# micro_RevB-328.net
KiCad netlist of a schematic drawn in EAGLE
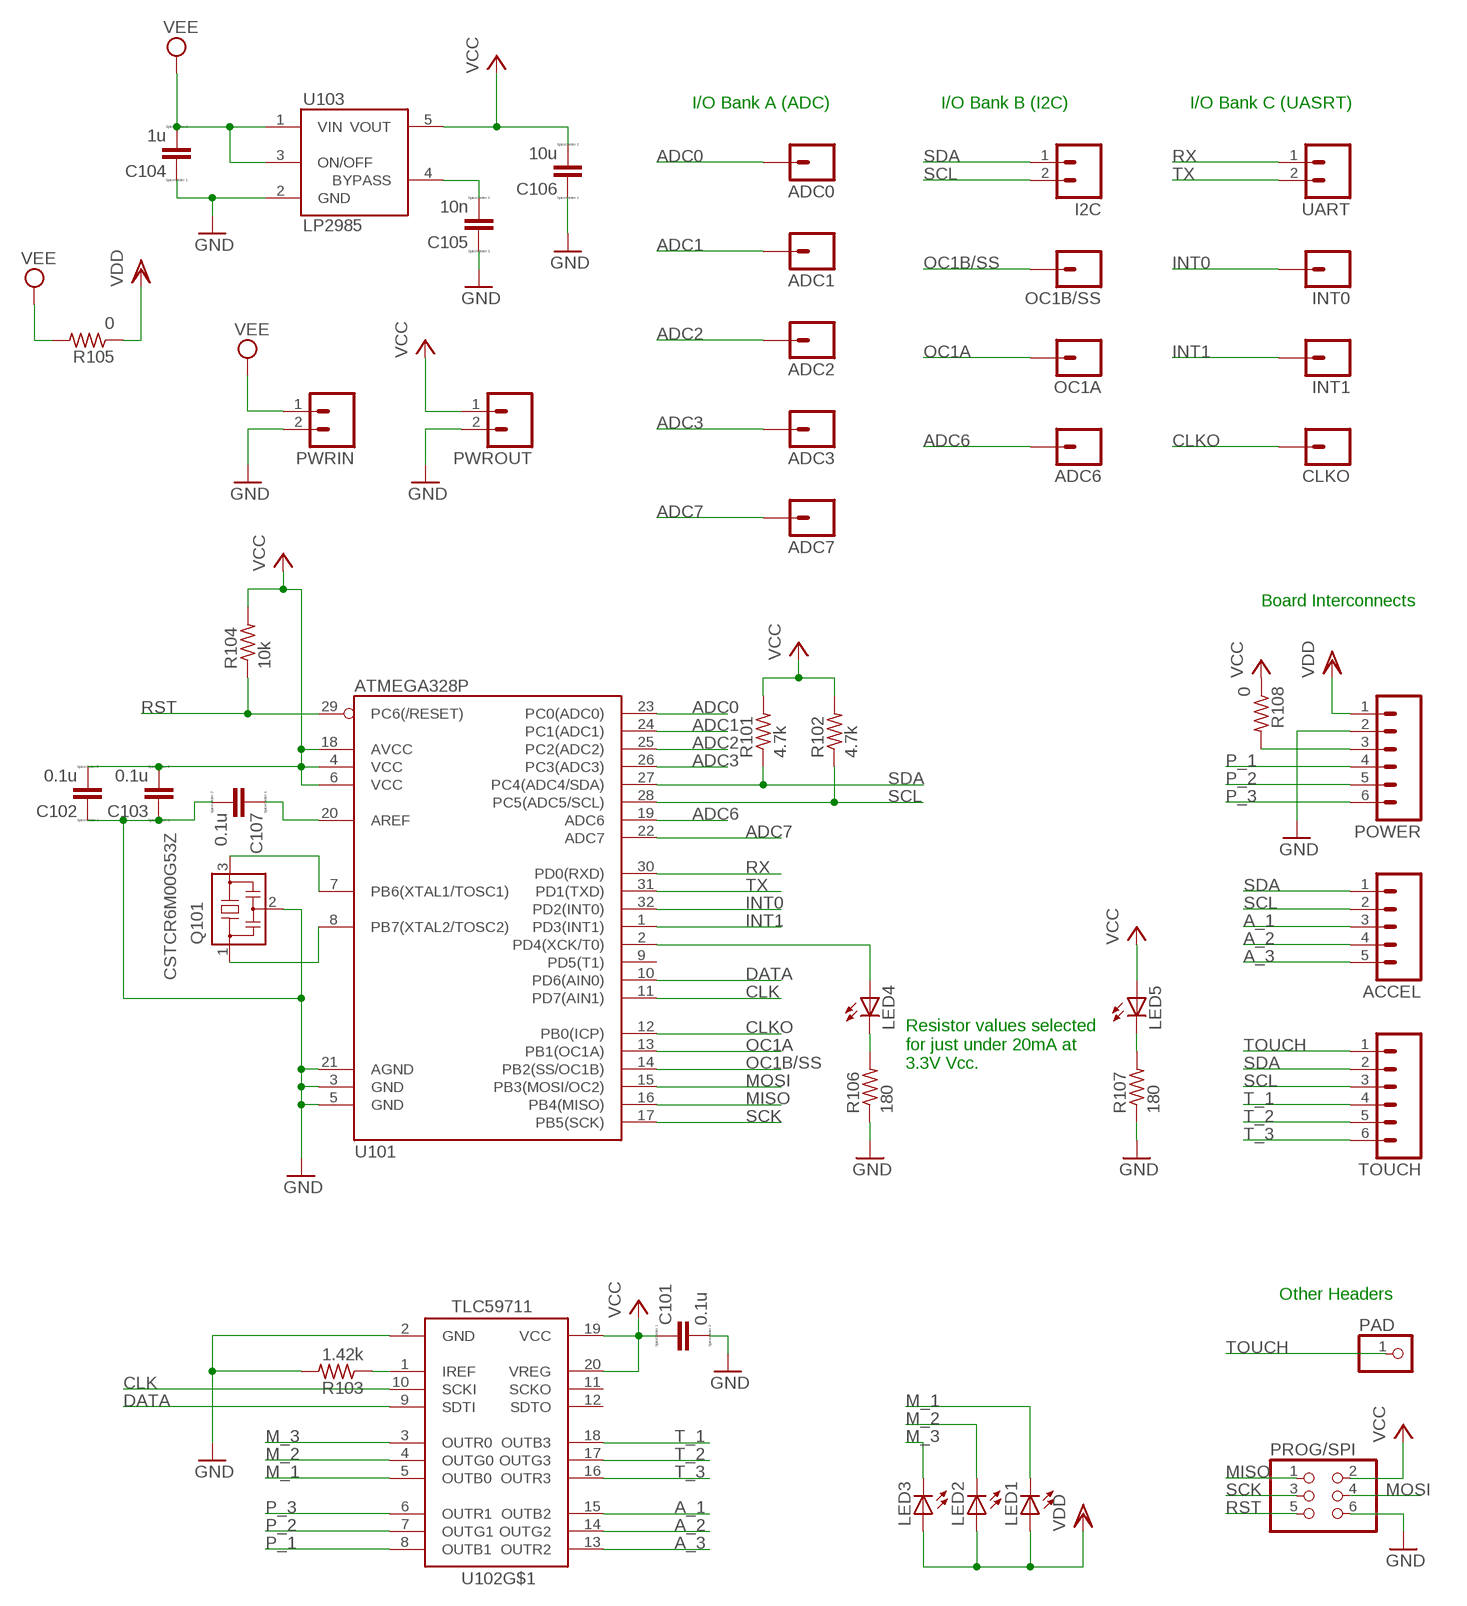
[diagram p0: schematic, sheet 1]

(export (version "E")
  (design (tool "Eeschema 10.0.6"))
  (components
    (comp (ref "ACCEL")
      (value "M05LOCK")
      (footprint "eagle-import:1X05_LOCK")
      (libsource (lib "eagle-import") (part "M05LOCK"))
    )
    (comp (ref "ADC0")
      (value "M01PTH")
      (footprint "eagle-import:1X01")
      (libsource (lib "eagle-import") (part "M01PTH"))
    )
    (comp (ref "ADC1")
      (value "M01PTH")
      (footprint "eagle-import:1X01")
      (libsource (lib "eagle-import") (part "M01PTH"))
    )
    (comp (ref "ADC2")
      (value "M01PTH")
      (footprint "eagle-import:1X01")
      (libsource (lib "eagle-import") (part "M01PTH"))
    )
    (comp (ref "ADC3")
      (value "M01PTH")
      (footprint "eagle-import:1X01")
      (libsource (lib "eagle-import") (part "M01PTH"))
    )
    (comp (ref "ADC6")
      (value "M01PTH")
      (footprint "eagle-import:1X01")
      (libsource (lib "eagle-import") (part "M01PTH"))
    )
    (comp (ref "ADC7")
      (value "M01PTH")
      (footprint "eagle-import:1X01")
      (libsource (lib "eagle-import") (part "M01PTH"))
    )
    (comp (ref "C101")
      (value "0.1u")
      (footprint "eagle-import:C0603")
      (libsource (lib "eagle-import") (part "CC0603"))
    )
    (comp (ref "C102")
      (value "0.1u")
      (footprint "eagle-import:C0603")
      (libsource (lib "eagle-import") (part "CC0603"))
    )
    (comp (ref "C103")
      (value "0.1u")
      (footprint "eagle-import:C0603")
      (libsource (lib "eagle-import") (part "CC0603"))
    )
    (comp (ref "C104")
      (value "1u")
      (footprint "eagle-import:C0603")
      (libsource (lib "eagle-import") (part "CC0603"))
    )
    (comp (ref "C105")
      (value "10n")
      (footprint "eagle-import:C0603")
      (libsource (lib "eagle-import") (part "CC0603"))
    )
    (comp (ref "C106")
      (value "10u")
      (footprint "eagle-import:C0603")
      (libsource (lib "eagle-import") (part "CC0603"))
    )
    (comp (ref "C107")
      (value "0.1u")
      (footprint "eagle-import:C0603")
      (libsource (lib "eagle-import") (part "CC0603"))
    )
    (comp (ref "CLKO")
      (value "M01PTH")
      (footprint "eagle-import:1X01")
      (libsource (lib "eagle-import") (part "M01PTH"))
    )
    (comp (ref "I2C")
      (value "M02LOCK")
      (footprint "eagle-import:1X02_LOCK")
      (libsource (lib "eagle-import") (part "M02LOCK"))
    )
    (comp (ref "INT0")
      (value "M01PTH")
      (footprint "eagle-import:1X01")
      (libsource (lib "eagle-import") (part "M01PTH"))
    )
    (comp (ref "INT1")
      (value "M01PTH")
      (footprint "eagle-import:1X01")
      (libsource (lib "eagle-import") (part "M01PTH"))
    )
    (comp (ref "LED1")
      (value "LEDP-LCC-4")
      (footprint "eagle-import:P-LCC-4")
      (libsource (lib "eagle-import") (part "LEDP-LCC-4"))
    )
    (comp (ref "LED2")
      (value "LEDP-LCC-4")
      (footprint "eagle-import:P-LCC-4")
      (libsource (lib "eagle-import") (part "LEDP-LCC-4"))
    )
    (comp (ref "LED3")
      (value "LEDP-LCC-4")
      (footprint "eagle-import:P-LCC-4")
      (libsource (lib "eagle-import") (part "LEDP-LCC-4"))
    )
    (comp (ref "LED4")
      (value "LEDSML0603")
      (footprint "eagle-import:SML0603")
      (libsource (lib "eagle-import") (part "LEDSML0603"))
    )
    (comp (ref "LED5")
      (value "LEDSML0603")
      (footprint "eagle-import:SML0603")
      (libsource (lib "eagle-import") (part "LEDSML0603"))
    )
    (comp (ref "OC1A")
      (value "M01PTH")
      (footprint "eagle-import:1X01")
      (libsource (lib "eagle-import") (part "M01PTH"))
    )
    (comp (ref "OC1B/SS")
      (value "M01PTH")
      (footprint "eagle-import:1X01")
      (libsource (lib "eagle-import") (part "M01PTH"))
    )
    (comp (ref "PAD")
      (value "PINHD-1X1")
      (footprint "eagle-import:1X01")
      (libsource (lib "eagle-import") (part "PINHD-1X1"))
    )
    (comp (ref "POWER")
      (value "M06SIP_LOCK")
      (footprint "eagle-import:1X06-SIP_LOCK")
      (libsource (lib "eagle-import") (part "M06SIP_LOCK"))
    )
    (comp (ref "PROG/SPI")
      (value "PINHD-2X3")
      (footprint "eagle-import:2X03")
      (libsource (lib "eagle-import") (part "PINHD-2X3"))
    )
    (comp (ref "PWRIN")
      (value "M02LOCK")
      (footprint "eagle-import:1X02_LOCK")
      (libsource (lib "eagle-import") (part "M02LOCK"))
    )
    (comp (ref "PWROUT")
      (value "M02LOCK")
      (footprint "eagle-import:1X02_LOCK")
      (libsource (lib "eagle-import") (part "M02LOCK"))
    )
    (comp (ref "Q101")
      (value "CSTCR6M00G53Z")
      (footprint "eagle-import:CSTCR6M")
      (fields (field (name "MPN") "CSTCR6M00G53-R0"))
      (libsource (lib "eagle-import") (part "CSTCR6M00G53Z"))
    )
    (comp (ref "R101")
      (value "4.7k")
      (footprint "eagle-import:R0603")
      (libsource (lib "eagle-import") (part "R-US_R0603"))
    )
    (comp (ref "R102")
      (value "4.7k")
      (footprint "eagle-import:R0603")
      (libsource (lib "eagle-import") (part "R-US_R0603"))
    )
    (comp (ref "R103")
      (value "1.42k")
      (footprint "eagle-import:R0603")
      (libsource (lib "eagle-import") (part "resistor_R-US_R0603"))
    )
    (comp (ref "R104")
      (value "10k")
      (footprint "eagle-import:R0603")
      (libsource (lib "eagle-import") (part "R-US_R0603"))
    )
    (comp (ref "R105")
      (value "0")
      (footprint "eagle-import:R0603")
      (libsource (lib "eagle-import") (part "R-US_R0603"))
    )
    (comp (ref "R106")
      (value "180")
      (footprint "eagle-import:R0603")
      (libsource (lib "eagle-import") (part "R-US_R0603"))
    )
    (comp (ref "R107")
      (value "180")
      (footprint "eagle-import:R0603")
      (libsource (lib "eagle-import") (part "R-US_R0603"))
    )
    (comp (ref "R108")
      (value "0")
      (footprint "eagle-import:R0603")
      (libsource (lib "eagle-import") (part "R-US_R0603"))
    )
    (comp (ref "TOUCH")
      (value "M06SIP_LOCK")
      (footprint "eagle-import:1X06-SIP_LOCK")
      (libsource (lib "eagle-import") (part "M06SIP_LOCK"))
    )
    (comp (ref "U101")
      (value "ATMEGA328P")
      (footprint "eagle-import:TQFP32-08")
      (libsource (lib "eagle-import") (part "ATMEGA328_SMT"))
    )
    (comp (ref "U102")
      (value "TLC59711")
      (footprint "eagle-import:HTSSOP20DAP")
      (libsource (lib "eagle-import") (part "TLC59711"))
    )
    (comp (ref "U103")
      (value "LP2985AIM5-3.3")
      (footprint "eagle-import:SOT25")
      (libsource (lib "eagle-import") (part "LP2985AIM5-3.3"))
    )
    (comp (ref "UART")
      (value "M02LOCK")
      (footprint "eagle-import:1X02_LOCK")
      (libsource (lib "eagle-import") (part "M02LOCK"))
    )
  )
  (nets
    (net (code "1") (name "/ADC0") (class "Default")
      (node (ref "ADC0") (pin "1") (pinfunction "1_1") (pintype "passive"))
      (node (ref "U101") (pin "23") (pinfunction "PC0(ADC0)_23") (pintype "bidirectional"))
    )
    (net (code "2") (name "/ADC1") (class "Default")
      (node (ref "ADC1") (pin "1") (pinfunction "1_1") (pintype "passive"))
      (node (ref "U101") (pin "24") (pinfunction "PC1(ADC1)_24") (pintype "bidirectional"))
    )
    (net (code "3") (name "/ADC2") (class "Default")
      (node (ref "ADC2") (pin "1") (pinfunction "1_1") (pintype "passive"))
      (node (ref "U101") (pin "25") (pinfunction "PC2(ADC2)_25") (pintype "bidirectional"))
    )
    (net (code "4") (name "/ADC3") (class "Default")
      (node (ref "ADC3") (pin "1") (pinfunction "1_1") (pintype "passive"))
      (node (ref "U101") (pin "26") (pinfunction "PC3(ADC3)_26") (pintype "bidirectional"))
    )
    (net (code "5") (name "/ADC6") (class "Default")
      (node (ref "ADC6") (pin "1") (pinfunction "1_1") (pintype "passive"))
      (node (ref "U101") (pin "19") (pinfunction "ADC6_19") (pintype "bidirectional"))
    )
    (net (code "6") (name "/ADC7") (class "Default")
      (node (ref "ADC7") (pin "1") (pinfunction "1_1") (pintype "passive"))
      (node (ref "U101") (pin "22") (pinfunction "ADC7_22") (pintype "bidirectional"))
    )
    (net (code "7") (name "/A_1") (class "Default")
      (node (ref "ACCEL") (pin "3") (pinfunction "3_3") (pintype "passive"))
      (node (ref "U102") (pin "15") (pinfunction "OUTB2_15") (pintype "open_collector"))
    )
    (net (code "8") (name "/A_2") (class "Default")
      (node (ref "ACCEL") (pin "4") (pinfunction "4_4") (pintype "passive"))
      (node (ref "U102") (pin "14") (pinfunction "OUTG2_14") (pintype "open_collector"))
    )
    (net (code "9") (name "/A_3") (class "Default")
      (node (ref "ACCEL") (pin "5") (pinfunction "5_5") (pintype "passive"))
      (node (ref "U102") (pin "13") (pinfunction "OUTR2_13") (pintype "open_collector"))
    )
    (net (code "10") (name "/CLK") (class "Default")
      (node (ref "U101") (pin "11") (pinfunction "PD7(AIN1)_11") (pintype "bidirectional"))
      (node (ref "U102") (pin "10") (pinfunction "SCKI_10") (pintype "input"))
    )
    (net (code "11") (name "/CLKO") (class "Default")
      (node (ref "CLKO") (pin "1") (pinfunction "1_1") (pintype "passive"))
      (node (ref "U101") (pin "12") (pinfunction "PB0(ICP)_12") (pintype "bidirectional"))
    )
    (net (code "12") (name "/DATA") (class "Default")
      (node (ref "U101") (pin "10") (pinfunction "PD6(AIN0)_10") (pintype "bidirectional"))
      (node (ref "U102") (pin "9") (pinfunction "SDTI_9") (pintype "input"))
    )
    (net (code "13") (name "/INT0") (class "Default")
      (node (ref "INT0") (pin "1") (pinfunction "1_1") (pintype "passive"))
      (node (ref "U101") (pin "32") (pinfunction "PD2(INT0)_32") (pintype "bidirectional"))
    )
    (net (code "14") (name "/INT1") (class "Default")
      (node (ref "INT1") (pin "1") (pinfunction "1_1") (pintype "passive"))
      (node (ref "U101") (pin "1") (pinfunction "PD3(INT1)_1") (pintype "bidirectional"))
    )
    (net (code "15") (name "/MISO") (class "Default")
      (node (ref "PROG/SPI") (pin "1") (pinfunction "1_1") (pintype "passive"))
      (node (ref "U101") (pin "16") (pinfunction "PB4(MISO)_16") (pintype "bidirectional"))
    )
    (net (code "16") (name "/MOSI") (class "Default")
      (node (ref "PROG/SPI") (pin "4") (pinfunction "4_4") (pintype "passive"))
      (node (ref "U101") (pin "15") (pinfunction "PB3(MOSI/OC2)_15") (pintype "bidirectional"))
    )
    (net (code "17") (name "/M_1") (class "Default")
      (node (ref "LED1") (pin "C@4") (pinfunction "C_C@4") (pintype "passive"))
      (node (ref "U102") (pin "5") (pinfunction "OUTB0_5") (pintype "open_collector"))
    )
    (net (code "18") (name "/M_2") (class "Default")
      (node (ref "LED2") (pin "C@4") (pinfunction "C_C@4") (pintype "passive"))
      (node (ref "U102") (pin "4") (pinfunction "OUTG0_4") (pintype "open_collector"))
    )
    (net (code "19") (name "/M_3") (class "Default")
      (node (ref "LED3") (pin "C@4") (pinfunction "C_C@4") (pintype "passive"))
      (node (ref "U102") (pin "3") (pinfunction "OUTR0_3") (pintype "open_collector"))
    )
    (net (code "20") (name "/OC1A") (class "Default")
      (node (ref "OC1A") (pin "1") (pinfunction "1_1") (pintype "passive"))
      (node (ref "U101") (pin "13") (pinfunction "PB1(OC1A)_13") (pintype "bidirectional"))
    )
    (net (code "21") (name "/OC1B{slash}SS") (class "Default")
      (node (ref "OC1B/SS") (pin "1") (pinfunction "1_1") (pintype "passive"))
      (node (ref "U101") (pin "14") (pinfunction "PB2(SS/OC1B)_14") (pintype "bidirectional"))
    )
    (net (code "22") (name "/P_1") (class "Default")
      (node (ref "POWER") (pin "4") (pinfunction "4_4") (pintype "passive"))
      (node (ref "U102") (pin "8") (pinfunction "OUTB1_8") (pintype "open_collector"))
    )
    (net (code "23") (name "/P_2") (class "Default")
      (node (ref "POWER") (pin "5") (pinfunction "5_5") (pintype "passive"))
      (node (ref "U102") (pin "7") (pinfunction "OUTG1_7") (pintype "open_collector"))
    )
    (net (code "24") (name "/P_3") (class "Default")
      (node (ref "POWER") (pin "6") (pinfunction "6_6") (pintype "passive"))
      (node (ref "U102") (pin "6") (pinfunction "OUTR1_6") (pintype "open_collector"))
    )
    (net (code "25") (name "/RST") (class "Default")
      (node (ref "PROG/SPI") (pin "5") (pinfunction "5_5") (pintype "passive"))
      (node (ref "R104") (pin "1") (pinfunction "1_1") (pintype "passive"))
      (node (ref "U101") (pin "29") (pinfunction "PC6(/RESET)_29") (pintype "bidirectional"))
    )
    (net (code "26") (name "/RX") (class "Default")
      (node (ref "U101") (pin "30") (pinfunction "PD0(RXD)_30") (pintype "bidirectional"))
      (node (ref "UART") (pin "1") (pinfunction "1_1") (pintype "passive"))
    )
    (net (code "27") (name "/SCK") (class "Default")
      (node (ref "PROG/SPI") (pin "3") (pinfunction "3_3") (pintype "passive"))
      (node (ref "U101") (pin "17") (pinfunction "PB5(SCK)_17") (pintype "bidirectional"))
    )
    (net (code "28") (name "/SCL") (class "Default")
      (node (ref "ACCEL") (pin "2") (pinfunction "2_2") (pintype "passive"))
      (node (ref "I2C") (pin "2") (pinfunction "2_2") (pintype "passive"))
      (node (ref "R102") (pin "1") (pinfunction "1_1") (pintype "passive"))
      (node (ref "TOUCH") (pin "3") (pinfunction "3_3") (pintype "passive"))
      (node (ref "U101") (pin "28") (pinfunction "PC5(ADC5/SCL)_28") (pintype "bidirectional"))
    )
    (net (code "29") (name "/SDA") (class "Default")
      (node (ref "ACCEL") (pin "1") (pinfunction "1_1") (pintype "passive"))
      (node (ref "I2C") (pin "1") (pinfunction "1_1") (pintype "passive"))
      (node (ref "R101") (pin "1") (pinfunction "1_1") (pintype "passive"))
      (node (ref "TOUCH") (pin "2") (pinfunction "2_2") (pintype "passive"))
      (node (ref "U101") (pin "27") (pinfunction "PC4(ADC4/SDA)_27") (pintype "bidirectional"))
    )
    (net (code "30") (name "/TOUCH") (class "Default")
      (node (ref "PAD") (pin "1") (pinfunction "1_1") (pintype "passive"))
      (node (ref "TOUCH") (pin "1") (pinfunction "1_1") (pintype "passive"))
    )
    (net (code "31") (name "/TX") (class "Default")
      (node (ref "U101") (pin "31") (pinfunction "PD1(TXD)_31") (pintype "bidirectional"))
      (node (ref "UART") (pin "2") (pinfunction "2_2") (pintype "passive"))
    )
    (net (code "32") (name "/T_1") (class "Default")
      (node (ref "TOUCH") (pin "4") (pinfunction "4_4") (pintype "passive"))
      (node (ref "U102") (pin "18") (pinfunction "OUTB3_18") (pintype "open_collector"))
    )
    (net (code "33") (name "/T_2") (class "Default")
      (node (ref "TOUCH") (pin "5") (pinfunction "5_5") (pintype "passive"))
      (node (ref "U102") (pin "17") (pinfunction "OUTG3_17") (pintype "open_collector"))
    )
    (net (code "34") (name "/T_3") (class "Default")
      (node (ref "TOUCH") (pin "6") (pinfunction "6_6") (pintype "passive"))
      (node (ref "U102") (pin "16") (pinfunction "OUTR3_16") (pintype "open_collector"))
    )
    (net (code "35") (name "GND") (class "Default")
      (node (ref "C101") (pin "2") (pinfunction "2_2") (pintype "passive"))
      (node (ref "C102") (pin "1") (pinfunction "1_1") (pintype "passive"))
      (node (ref "C103") (pin "1") (pinfunction "1_1") (pintype "passive"))
      (node (ref "C104") (pin "1") (pinfunction "1_1") (pintype "passive"))
      (node (ref "C105") (pin "1") (pinfunction "1_1") (pintype "passive"))
      (node (ref "C106") (pin "1") (pinfunction "1_1") (pintype "passive"))
      (node (ref "C107") (pin "2") (pinfunction "2_2") (pintype "passive"))
      (node (ref "POWER") (pin "2") (pinfunction "2_2") (pintype "passive"))
      (node (ref "PROG/SPI") (pin "6") (pinfunction "6_6") (pintype "passive"))
      (node (ref "PWRIN") (pin "2") (pinfunction "2_2") (pintype "passive"))
      (node (ref "PWROUT") (pin "2") (pinfunction "2_2") (pintype "passive"))
      (node (ref "Q101") (pin "2") (pinfunction "2_2") (pintype "passive"))
      (node (ref "R103") (pin "2") (pinfunction "2_2") (pintype "passive"))
      (node (ref "R106") (pin "1") (pinfunction "1_1") (pintype "passive"))
      (node (ref "R107") (pin "1") (pinfunction "1_1") (pintype "passive"))
      (node (ref "U101") (pin "21") (pinfunction "AGND_21") (pintype "bidirectional"))
      (node (ref "U101") (pin "3") (pinfunction "GND_3") (pintype "bidirectional"))
      (node (ref "U101") (pin "5") (pinfunction "GND_5") (pintype "bidirectional"))
      (node (ref "U102") (pin "2") (pinfunction "GND_2") (pintype "power_in"))
      (node (ref "U103") (pin "2") (pinfunction "GND_2") (pintype "power_in"))
    )
    (net (code "36") (name "Net-(LED4-PadC)") (class "Default")
      (node (ref "LED4") (pin "C") (pinfunction "C_C") (pintype "passive"))
      (node (ref "R106") (pin "2") (pinfunction "2_2") (pintype "passive"))
    )
    (net (code "37") (name "Net-(LED5-PadC)") (class "Default")
      (node (ref "LED5") (pin "C") (pinfunction "C_C") (pintype "passive"))
      (node (ref "R107") (pin "2") (pinfunction "2_2") (pintype "passive"))
    )
    (net (code "38") (name "Net-(POWER-Pad3)") (class "Default")
      (node (ref "POWER") (pin "3") (pinfunction "3_3") (pintype "passive"))
      (node (ref "R108") (pin "2") (pinfunction "2_2") (pintype "passive"))
    )
    (net (code "39") (name "Net-(U101-AREF)") (class "Default")
      (node (ref "C107") (pin "1") (pinfunction "1_1") (pintype "passive"))
      (node (ref "U101") (pin "20") (pinfunction "AREF_20") (pintype "bidirectional"))
    )
    (net (code "40") (name "Net-(U101-PB6(XTAL1{slash}TOSC1))") (class "Default")
      (node (ref "Q101") (pin "3") (pinfunction "3_3") (pintype "passive"))
      (node (ref "U101") (pin "7") (pinfunction "PB6(XTAL1/TOSC1)_7") (pintype "bidirectional"))
    )
    (net (code "41") (name "Net-(U101-PB7(XTAL2{slash}TOSC2))") (class "Default")
      (node (ref "Q101") (pin "1") (pinfunction "1_1") (pintype "passive"))
      (node (ref "U101") (pin "8") (pinfunction "PB7(XTAL2/TOSC2)_8") (pintype "bidirectional"))
    )
    (net (code "42") (name "Net-(U101-PD4(XCK{slash}T0))") (class "Default")
      (node (ref "LED4") (pin "A") (pinfunction "A_A") (pintype "passive"))
      (node (ref "U101") (pin "2") (pinfunction "PD4(XCK/T0)_2") (pintype "bidirectional"))
    )
    (net (code "43") (name "Net-(U102A-IREF)") (class "Default")
      (node (ref "R103") (pin "1") (pinfunction "1_1") (pintype "passive"))
      (node (ref "U102") (pin "1") (pinfunction "IREF_1") (pintype "bidirectional"))
    )
    (net (code "44") (name "Net-(U103-BYPASS)") (class "Default")
      (node (ref "C105") (pin "2") (pinfunction "2_2") (pintype "passive"))
      (node (ref "U103") (pin "4") (pinfunction "BYPASS_4") (pintype "power_in"))
    )
    (net (code "45") (name "VCC") (class "Default")
      (node (ref "C101") (pin "1") (pinfunction "1_1") (pintype "passive"))
      (node (ref "C102") (pin "2") (pinfunction "2_2") (pintype "passive"))
      (node (ref "C103") (pin "2") (pinfunction "2_2") (pintype "passive"))
      (node (ref "C106") (pin "2") (pinfunction "2_2") (pintype "passive"))
      (node (ref "LED5") (pin "A") (pinfunction "A_A") (pintype "passive"))
      (node (ref "PROG/SPI") (pin "2") (pinfunction "2_2") (pintype "passive"))
      (node (ref "PWROUT") (pin "1") (pinfunction "1_1") (pintype "passive"))
      (node (ref "R101") (pin "2") (pinfunction "2_2") (pintype "passive"))
      (node (ref "R102") (pin "2") (pinfunction "2_2") (pintype "passive"))
      (node (ref "R104") (pin "2") (pinfunction "2_2") (pintype "passive"))
      (node (ref "R108") (pin "1") (pinfunction "1_1") (pintype "passive"))
      (node (ref "U101") (pin "18") (pinfunction "AVCC_18") (pintype "bidirectional"))
      (node (ref "U101") (pin "4") (pinfunction "VCC_4") (pintype "bidirectional"))
      (node (ref "U101") (pin "6") (pinfunction "VCC_6") (pintype "bidirectional"))
      (node (ref "U102") (pin "19") (pinfunction "VCC_19") (pintype "power_in"))
      (node (ref "U102") (pin "20") (pinfunction "VREG_20") (pintype "bidirectional"))
      (node (ref "U103") (pin "5") (pinfunction "VOUT_5") (pintype "power_in"))
    )
    (net (code "46") (name "VDD") (class "Default")
      (node (ref "LED1") (pin "A") (pinfunction "A_A") (pintype "passive"))
      (node (ref "LED2") (pin "A") (pinfunction "A_A") (pintype "passive"))
      (node (ref "LED3") (pin "A") (pinfunction "A_A") (pintype "passive"))
      (node (ref "POWER") (pin "1") (pinfunction "1_1") (pintype "passive"))
      (node (ref "R105") (pin "1") (pinfunction "1_1") (pintype "passive"))
    )
    (net (code "47") (name "VEE") (class "Default")
      (node (ref "C104") (pin "2") (pinfunction "2_2") (pintype "passive"))
      (node (ref "PWRIN") (pin "1") (pinfunction "1_1") (pintype "passive"))
      (node (ref "R105") (pin "2") (pinfunction "2_2") (pintype "passive"))
      (node (ref "U103") (pin "1") (pinfunction "VIN_1") (pintype "power_in"))
      (node (ref "U103") (pin "3") (pinfunction "ON/OFF_3") (pintype "input"))
    )
    (net (code "48") (name "unconnected-(U101-PD5(T1)-Pad9)") (class "Default")
      (node (ref "U101") (pin "9") (pinfunction "PD5(T1)_9") (pintype "bidirectional"))
    )
    (net (code "49") (name "unconnected-(U102A-SCKO-Pad11)") (class "Default")
      (node (ref "U102") (pin "11") (pinfunction "SCKO_11") (pintype "output"))
    )
    (net (code "50") (name "unconnected-(U102A-SDTO-Pad12)") (class "Default")
      (node (ref "U102") (pin "12") (pinfunction "SDTO_12") (pintype "output"))
    )
  )
)
